# powerpack.net
KiCad netlist of a schematic drawn in EAGLE
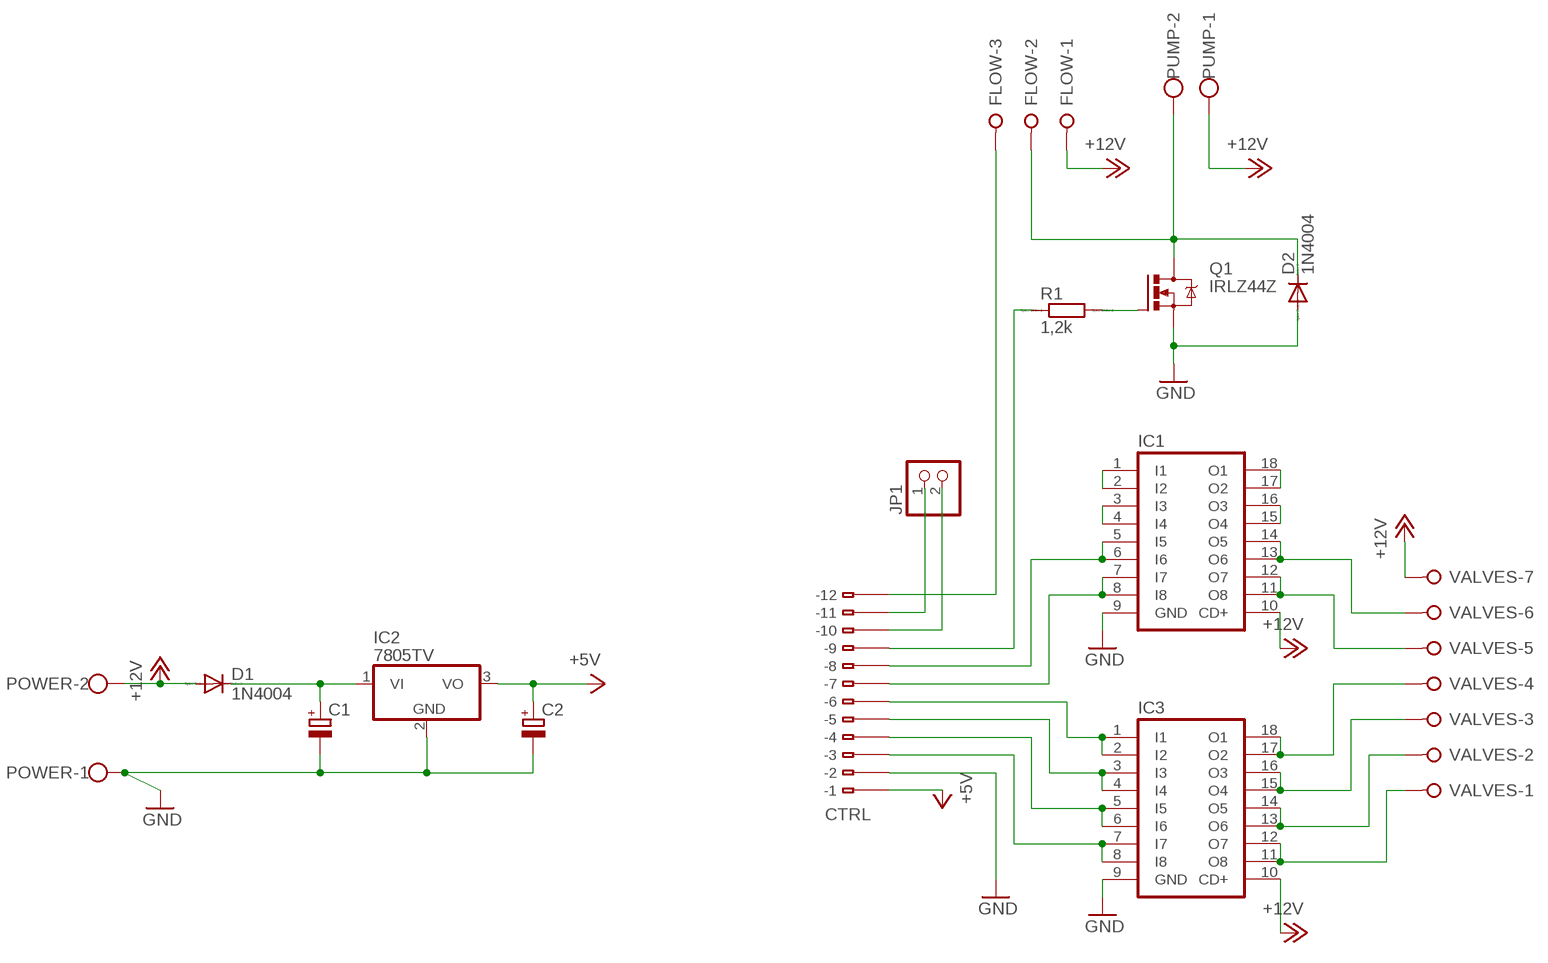
[diagram p0: schematic, sheet 1]

(export (version "E")
  (design (tool "Eeschema 10.0.6"))
  (components
    (comp (ref "C1")
      (value "CPOL-EUE2.5-7")
      (footprint "eagle-import:E2,5-7")
      (libsource (lib "eagle-import") (part "CPOL-EUE2.5-7"))
    )
    (comp (ref "C2")
      (value "CPOL-EUE2.5-7")
      (footprint "eagle-import:E2,5-7")
      (libsource (lib "eagle-import") (part "CPOL-EUE2.5-7"))
    )
    (comp (ref "CTRL")
      (value "233-112")
      (footprint "eagle-import:233-112")
      (libsource (lib "eagle-import") (part "233-112"))
    )
    (comp (ref "D1")
      (value "1N4004")
      (footprint "eagle-import:DO41-10")
      (libsource (lib "eagle-import") (part "1N4004"))
    )
    (comp (ref "D2")
      (value "1N4004")
      (footprint "eagle-import:DO41-10")
      (libsource (lib "eagle-import") (part "1N4004"))
    )
    (comp (ref "FLOW")
      (value "W237-03P")
      (footprint "eagle-import:W237-133")
      (libsource (lib "eagle-import") (part "W237-03P"))
    )
    (comp (ref "IC1")
      (value "ULN2803A")
      (footprint "eagle-import:DIL18")
      (libsource (lib "eagle-import") (part "ULN2803A"))
    )
    (comp (ref "IC2")
      (value "7805TV")
      (footprint "eagle-import:TO220V")
      (libsource (lib "eagle-import") (part "78TV05"))
    )
    (comp (ref "IC3")
      (value "ULN2803A")
      (footprint "eagle-import:DIL18")
      (libsource (lib "eagle-import") (part "ULN2803A"))
    )
    (comp (ref "JP1")
      (value "PINHD-1X2")
      (footprint "eagle-import:1X02")
      (libsource (lib "eagle-import") (part "PINHD-1X2"))
    )
    (comp (ref "POWER")
      (value "W237-102")
      (footprint "eagle-import:W237-102")
      (fields (field (name "MPN") "237-102"))
      (libsource (lib "eagle-import") (part "W237-102"))
    )
    (comp (ref "PUMP")
      (value "W237-102")
      (footprint "eagle-import:W237-102")
      (fields (field (name "MPN") "237-102"))
      (libsource (lib "eagle-import") (part "W237-102"))
    )
    (comp (ref "Q1")
      (value "IRLZ44Z")
      (footprint "eagle-import:TO220BH")
      (libsource (lib "eagle-import") (part "IRLZ44Z"))
    )
    (comp (ref "R1")
      (value "1,2k")
      (footprint "eagle-import:0207_10")
      (libsource (lib "eagle-import") (part "R0207/10"))
    )
    (comp (ref "VALVES")
      (value "W237-07P")
      (footprint "eagle-import:W237-7P")
      (libsource (lib "eagle-import") (part "W237-07P"))
    )
  )
  (nets
    (net (code "1") (name "+5V") (class "Default")
      (node (ref "C2") (pin "+") (pinfunction "+_+") (pintype "passive"))
      (node (ref "CTRL") (pin "B1") (pinfunction "B-1_B1") (pintype "passive"))
      (node (ref "IC2") (pin "3") (pinfunction "VO_3") (pintype "passive"))
    )
    (net (code "2") (name "+12V") (class "Default")
      (node (ref "D1") (pin "A") (pinfunction "A_A") (pintype "passive"))
      (node (ref "FLOW") (pin "1") (pinfunction "KL_1") (pintype "passive"))
      (node (ref "IC1") (pin "10") (pinfunction "CD+_10") (pintype "passive"))
      (node (ref "IC3") (pin "10") (pinfunction "CD+_10") (pintype "passive"))
      (node (ref "POWER") (pin "2") (pinfunction "KL_2") (pintype "passive"))
      (node (ref "PUMP") (pin "1") (pinfunction "KL_1") (pintype "passive"))
      (node (ref "VALVES") (pin "7") (pinfunction "KL_7") (pintype "passive"))
    )
    (net (code "3") (name "GND") (class "Default")
      (node (ref "C1") (pin "-") (pinfunction "-_-") (pintype "passive"))
      (node (ref "C2") (pin "-") (pinfunction "-_-") (pintype "passive"))
      (node (ref "CTRL") (pin "B2") (pinfunction "B-2_B2") (pintype "passive"))
      (node (ref "D2") (pin "A") (pinfunction "A_A") (pintype "passive"))
      (node (ref "IC1") (pin "9") (pinfunction "GND_9") (pintype "power_in"))
      (node (ref "IC2") (pin "2") (pinfunction "GND_2") (pintype "passive"))
      (node (ref "IC3") (pin "9") (pinfunction "GND_9") (pintype "power_in"))
      (node (ref "POWER") (pin "1") (pinfunction "KL_1") (pintype "passive"))
      (node (ref "Q1") (pin "S") (pinfunction "S_S") (pintype "passive"))
    )
    (net (code "4") (name "Net-(CTRL-B-3)") (class "Default")
      (node (ref "CTRL") (pin "B3") (pinfunction "B-3_B3") (pintype "passive"))
      (node (ref "IC3") (pin "7") (pinfunction "I7_7") (pintype "input"))
      (node (ref "IC3") (pin "8") (pinfunction "I8_8") (pintype "input"))
    )
    (net (code "5") (name "Net-(CTRL-B-4)") (class "Default")
      (node (ref "CTRL") (pin "B4") (pinfunction "B-4_B4") (pintype "passive"))
      (node (ref "IC3") (pin "5") (pinfunction "I5_5") (pintype "input"))
      (node (ref "IC3") (pin "6") (pinfunction "I6_6") (pintype "input"))
    )
    (net (code "6") (name "Net-(CTRL-B-5)") (class "Default")
      (node (ref "CTRL") (pin "B5") (pinfunction "B-5_B5") (pintype "passive"))
      (node (ref "IC3") (pin "3") (pinfunction "I3_3") (pintype "input"))
      (node (ref "IC3") (pin "4") (pinfunction "I4_4") (pintype "input"))
    )
    (net (code "7") (name "Net-(CTRL-B-6)") (class "Default")
      (node (ref "CTRL") (pin "B6") (pinfunction "B-6_B6") (pintype "passive"))
      (node (ref "IC3") (pin "1") (pinfunction "I1_1") (pintype "input"))
      (node (ref "IC3") (pin "2") (pinfunction "I2_2") (pintype "input"))
    )
    (net (code "8") (name "Net-(CTRL-B-7)") (class "Default")
      (node (ref "CTRL") (pin "B7") (pinfunction "B-7_B7") (pintype "passive"))
      (node (ref "IC1") (pin "7") (pinfunction "I7_7") (pintype "input"))
      (node (ref "IC1") (pin "8") (pinfunction "I8_8") (pintype "input"))
    )
    (net (code "9") (name "Net-(CTRL-B-8)") (class "Default")
      (node (ref "CTRL") (pin "B8") (pinfunction "B-8_B8") (pintype "passive"))
      (node (ref "IC1") (pin "5") (pinfunction "I5_5") (pintype "input"))
      (node (ref "IC1") (pin "6") (pinfunction "I6_6") (pintype "input"))
    )
    (net (code "10") (name "Net-(CTRL-B-9)") (class "Default")
      (node (ref "CTRL") (pin "B9") (pinfunction "B-9_B9") (pintype "passive"))
      (node (ref "R1") (pin "1") (pinfunction "1_1") (pintype "passive"))
    )
    (net (code "11") (name "Net-(CTRL-B-10)") (class "Default")
      (node (ref "CTRL") (pin "B10") (pinfunction "B-10_B10") (pintype "passive"))
      (node (ref "JP1") (pin "2") (pinfunction "2_2") (pintype "passive"))
    )
    (net (code "12") (name "Net-(CTRL-B-11)") (class "Default")
      (node (ref "CTRL") (pin "B11") (pinfunction "B-11_B11") (pintype "passive"))
      (node (ref "JP1") (pin "1") (pinfunction "1_1") (pintype "passive"))
    )
    (net (code "13") (name "Net-(CTRL-B-12)") (class "Default")
      (node (ref "CTRL") (pin "B12") (pinfunction "B-12_B12") (pintype "passive"))
      (node (ref "FLOW") (pin "3") (pinfunction "KL_3") (pintype "passive"))
    )
    (net (code "14") (name "Net-(FLOWB-KL)") (class "Default")
      (node (ref "D2") (pin "C") (pinfunction "C_C") (pintype "passive"))
      (node (ref "FLOW") (pin "2") (pinfunction "KL_2") (pintype "passive"))
      (node (ref "PUMP") (pin "2") (pinfunction "KL_2") (pintype "passive"))
      (node (ref "Q1") (pin "D") (pinfunction "D_D") (pintype "passive"))
    )
    (net (code "15") (name "Net-(IC1-I1)") (class "Default")
      (node (ref "IC1") (pin "1") (pinfunction "I1_1") (pintype "input"))
      (node (ref "IC1") (pin "2") (pinfunction "I2_2") (pintype "input"))
    )
    (net (code "16") (name "Net-(IC1-I3)") (class "Default")
      (node (ref "IC1") (pin "3") (pinfunction "I3_3") (pintype "input"))
      (node (ref "IC1") (pin "4") (pinfunction "I4_4") (pintype "input"))
    )
    (net (code "17") (name "Net-(IC1-O1)") (class "Default")
      (node (ref "IC1") (pin "17") (pinfunction "O2_17") (pintype "open_collector"))
      (node (ref "IC1") (pin "18") (pinfunction "O1_18") (pintype "open_collector"))
    )
    (net (code "18") (name "Net-(IC1-O3)") (class "Default")
      (node (ref "IC1") (pin "15") (pinfunction "O4_15") (pintype "open_collector"))
      (node (ref "IC1") (pin "16") (pinfunction "O3_16") (pintype "open_collector"))
    )
    (net (code "19") (name "Net-(IC1-O5)") (class "Default")
      (node (ref "IC1") (pin "13") (pinfunction "O6_13") (pintype "open_collector"))
      (node (ref "IC1") (pin "14") (pinfunction "O5_14") (pintype "open_collector"))
      (node (ref "VALVES") (pin "6") (pinfunction "KL_6") (pintype "passive"))
    )
    (net (code "20") (name "Net-(IC1-O7)") (class "Default")
      (node (ref "IC1") (pin "11") (pinfunction "O8_11") (pintype "open_collector"))
      (node (ref "IC1") (pin "12") (pinfunction "O7_12") (pintype "open_collector"))
      (node (ref "VALVES") (pin "5") (pinfunction "KL_5") (pintype "passive"))
    )
    (net (code "21") (name "Net-(IC2-VI)") (class "Default")
      (node (ref "C1") (pin "+") (pinfunction "+_+") (pintype "passive"))
      (node (ref "D1") (pin "C") (pinfunction "C_C") (pintype "passive"))
      (node (ref "IC2") (pin "1") (pinfunction "VI_1") (pintype "input"))
    )
    (net (code "22") (name "Net-(IC3-O1)") (class "Default")
      (node (ref "IC3") (pin "17") (pinfunction "O2_17") (pintype "open_collector"))
      (node (ref "IC3") (pin "18") (pinfunction "O1_18") (pintype "open_collector"))
      (node (ref "VALVES") (pin "4") (pinfunction "KL_4") (pintype "passive"))
    )
    (net (code "23") (name "Net-(IC3-O3)") (class "Default")
      (node (ref "IC3") (pin "15") (pinfunction "O4_15") (pintype "open_collector"))
      (node (ref "IC3") (pin "16") (pinfunction "O3_16") (pintype "open_collector"))
      (node (ref "VALVES") (pin "3") (pinfunction "KL_3") (pintype "passive"))
    )
    (net (code "24") (name "Net-(IC3-O5)") (class "Default")
      (node (ref "IC3") (pin "13") (pinfunction "O6_13") (pintype "open_collector"))
      (node (ref "IC3") (pin "14") (pinfunction "O5_14") (pintype "open_collector"))
      (node (ref "VALVES") (pin "2") (pinfunction "KL_2") (pintype "passive"))
    )
    (net (code "25") (name "Net-(IC3-O7)") (class "Default")
      (node (ref "IC3") (pin "11") (pinfunction "O8_11") (pintype "open_collector"))
      (node (ref "IC3") (pin "12") (pinfunction "O7_12") (pintype "open_collector"))
      (node (ref "VALVES") (pin "1") (pinfunction "KL_1") (pintype "passive"))
    )
    (net (code "26") (name "Net-(Q1-PadG)") (class "Default")
      (node (ref "Q1") (pin "G") (pinfunction "G_G") (pintype "passive"))
      (node (ref "R1") (pin "2") (pinfunction "2_2") (pintype "passive"))
    )
    (net (code "27") (name "unconnected-(CTRL--1-PadA1)") (class "Default")
      (node (ref "CTRL") (pin "A1") (pinfunction "-1_A1") (pintype "passive"))
    )
    (net (code "28") (name "unconnected-(CTRL--2-PadA2)") (class "Default")
      (node (ref "CTRL") (pin "A2") (pinfunction "-2_A2") (pintype "passive"))
    )
    (net (code "29") (name "unconnected-(CTRL--3-PadA3)") (class "Default")
      (node (ref "CTRL") (pin "A3") (pinfunction "-3_A3") (pintype "passive"))
    )
    (net (code "30") (name "unconnected-(CTRL--4-PadA4)") (class "Default")
      (node (ref "CTRL") (pin "A4") (pinfunction "-4_A4") (pintype "passive"))
    )
    (net (code "31") (name "unconnected-(CTRL--5-PadA5)") (class "Default")
      (node (ref "CTRL") (pin "A5") (pinfunction "-5_A5") (pintype "passive"))
    )
    (net (code "32") (name "unconnected-(CTRL--6-PadA6)") (class "Default")
      (node (ref "CTRL") (pin "A6") (pinfunction "-6_A6") (pintype "passive"))
    )
    (net (code "33") (name "unconnected-(CTRL--7-PadA7)") (class "Default")
      (node (ref "CTRL") (pin "A7") (pinfunction "-7_A7") (pintype "passive"))
    )
    (net (code "34") (name "unconnected-(CTRL--8-PadA8)") (class "Default")
      (node (ref "CTRL") (pin "A8") (pinfunction "-8_A8") (pintype "passive"))
    )
    (net (code "35") (name "unconnected-(CTRL--9-PadA9)") (class "Default")
      (node (ref "CTRL") (pin "A9") (pinfunction "-9_A9") (pintype "passive"))
    )
    (net (code "36") (name "unconnected-(CTRL--10-PadA10)") (class "Default")
      (node (ref "CTRL") (pin "A10") (pinfunction "-10_A10") (pintype "passive"))
    )
    (net (code "37") (name "unconnected-(CTRL--11-PadA11)") (class "Default")
      (node (ref "CTRL") (pin "A11") (pinfunction "-11_A11") (pintype "passive"))
    )
    (net (code "38") (name "unconnected-(CTRL--12-PadA12)") (class "Default")
      (node (ref "CTRL") (pin "A12") (pinfunction "-12_A12") (pintype "passive"))
    )
  )
)
